# GPSReceiver_Kenwood710.net
KiCad netlist of a schematic drawn in EAGLE
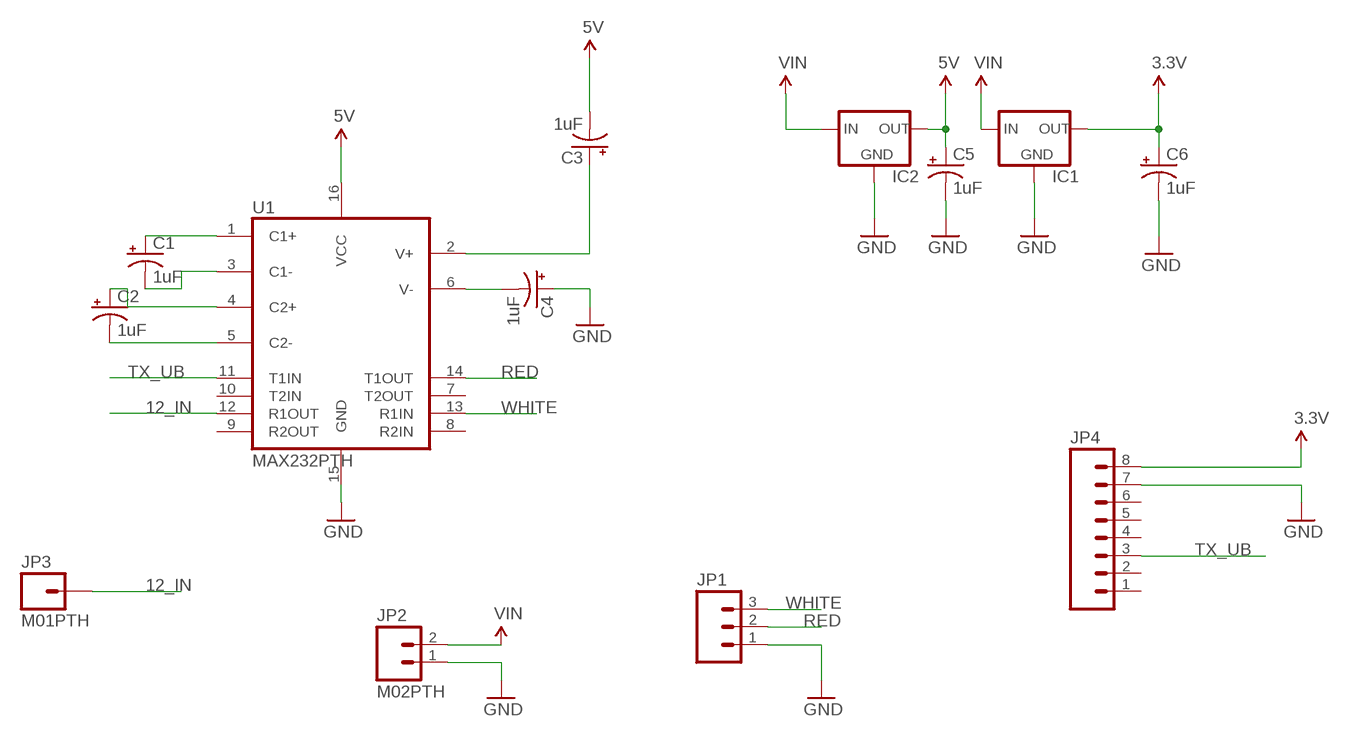
[diagram p0: schematic, sheet 1]

(export (version "E")
  (design (tool "Eeschema 10.0.6"))
  (components
    (comp (ref "C1")
      (value "1uF")
      (footprint "eagle-import:CPOL-RADIAL-10UF-25V")
      (libsource (lib "eagle-import") (part "CAP_POLPTH2"))
    )
    (comp (ref "C2")
      (value "1uF")
      (footprint "eagle-import:CPOL-RADIAL-10UF-25V")
      (libsource (lib "eagle-import") (part "CAP_POLPTH2"))
    )
    (comp (ref "C3")
      (value "1uF")
      (footprint "eagle-import:CPOL-RADIAL-10UF-25V")
      (libsource (lib "eagle-import") (part "CAP_POLPTH2"))
    )
    (comp (ref "C4")
      (value "1uF")
      (footprint "eagle-import:CPOL-RADIAL-10UF-25V")
      (libsource (lib "eagle-import") (part "CAP_POLPTH2"))
    )
    (comp (ref "C5")
      (value "1uF")
      (footprint "eagle-import:CPOL-RADIAL-10UF-25V")
      (libsource (lib "eagle-import") (part "CAP_POLPTH2"))
    )
    (comp (ref "C6")
      (value "1uF")
      (footprint "eagle-import:CPOL-RADIAL-10UF-25V")
      (libsource (lib "eagle-import") (part "CAP_POLPTH2"))
    )
    (comp (ref "IC1")
      (value "V_REG_78XX-TO-220")
      (footprint "eagle-import:TO-220-ALT")
      (libsource (lib "eagle-import") (part "V_REG_78XX-TO-220"))
    )
    (comp (ref "IC2")
      (value "V_REG_78XX-TO-220")
      (footprint "eagle-import:TO-220-ALT")
      (libsource (lib "eagle-import") (part "V_REG_78XX-TO-220"))
    )
    (comp (ref "JP1")
      (value "M03PTH")
      (footprint "eagle-import:1X03")
      (libsource (lib "eagle-import") (part "M03PTH"))
    )
    (comp (ref "JP2")
      (value "M02PTH")
      (footprint "eagle-import:1X02")
      (libsource (lib "eagle-import") (part "M02PTH"))
    )
    (comp (ref "JP3")
      (value "M01PTH")
      (footprint "eagle-import:1X01")
      (libsource (lib "eagle-import") (part "M01PTH"))
    )
    (comp (ref "JP4")
      (value "M08LOCK")
      (footprint "eagle-import:1X08_LOCK")
      (libsource (lib "eagle-import") (part "M08LOCK"))
    )
    (comp (ref "U1")
      (value "MAX232PTH")
      (footprint "eagle-import:DIL16")
      (libsource (lib "eagle-import") (part "MAX232PTH"))
    )
  )
  (nets
    (net (code "1") (name "/12_IN") (class "Default")
      (node (ref "JP3") (pin "1") (pinfunction "1_1") (pintype "passive"))
      (node (ref "U1") (pin "12") (pinfunction "R1OUT_12") (pintype "output"))
    )
    (net (code "2") (name "/RED") (class "Default")
      (node (ref "JP1") (pin "2") (pinfunction "2_2") (pintype "passive"))
      (node (ref "U1") (pin "14") (pinfunction "T1OUT_14") (pintype "output"))
    )
    (net (code "3") (name "/TX_UB") (class "Default")
      (node (ref "JP4") (pin "3") (pinfunction "3_3") (pintype "passive"))
      (node (ref "U1") (pin "11") (pinfunction "T1IN_11") (pintype "input"))
    )
    (net (code "4") (name "/WHITE") (class "Default")
      (node (ref "JP1") (pin "3") (pinfunction "3_3") (pintype "passive"))
      (node (ref "U1") (pin "13") (pinfunction "R1IN_13") (pintype "input"))
    )
    (net (code "5") (name "3.3V") (class "Default")
      (node (ref "C6") (pin "1") (pinfunction "+_1") (pintype "passive"))
      (node (ref "IC1") (pin "OUT") (pinfunction "OUT_OUT") (pintype "output"))
      (node (ref "JP4") (pin "8") (pinfunction "8_8") (pintype "passive"))
    )
    (net (code "6") (name "5V") (class "Default")
      (node (ref "C3") (pin "2") (pinfunction "-_2") (pintype "passive"))
      (node (ref "C5") (pin "1") (pinfunction "+_1") (pintype "passive"))
      (node (ref "IC2") (pin "OUT") (pinfunction "OUT_OUT") (pintype "output"))
      (node (ref "U1") (pin "16") (pinfunction "VCC_16") (pintype "bidirectional"))
    )
    (net (code "7") (name "GND") (class "Default")
      (node (ref "C4") (pin "1") (pinfunction "+_1") (pintype "passive"))
      (node (ref "C5") (pin "2") (pinfunction "-_2") (pintype "passive"))
      (node (ref "C6") (pin "2") (pinfunction "-_2") (pintype "passive"))
      (node (ref "IC1") (pin "GND") (pinfunction "GND_GND") (pintype "input"))
      (node (ref "IC2") (pin "GND") (pinfunction "GND_GND") (pintype "input"))
      (node (ref "JP1") (pin "1") (pinfunction "1_1") (pintype "passive"))
      (node (ref "JP2") (pin "1") (pinfunction "1_1") (pintype "passive"))
      (node (ref "JP4") (pin "7") (pinfunction "7_7") (pintype "passive"))
      (node (ref "U1") (pin "15") (pinfunction "GND_15") (pintype "bidirectional"))
    )
    (net (code "8") (name "Net-(C1-+)") (class "Default")
      (node (ref "C1") (pin "1") (pinfunction "+_1") (pintype "passive"))
      (node (ref "U1") (pin "1") (pinfunction "C1+_1") (pintype "bidirectional"))
    )
    (net (code "9") (name "Net-(C1--)") (class "Default")
      (node (ref "C1") (pin "2") (pinfunction "-_2") (pintype "passive"))
      (node (ref "U1") (pin "3") (pinfunction "C1-_3") (pintype "bidirectional"))
    )
    (net (code "10") (name "Net-(C2-+)") (class "Default")
      (node (ref "C2") (pin "1") (pinfunction "+_1") (pintype "passive"))
      (node (ref "U1") (pin "4") (pinfunction "C2+_4") (pintype "bidirectional"))
    )
    (net (code "11") (name "Net-(C2--)") (class "Default")
      (node (ref "C2") (pin "2") (pinfunction "-_2") (pintype "passive"))
      (node (ref "U1") (pin "5") (pinfunction "C2-_5") (pintype "bidirectional"))
    )
    (net (code "12") (name "Net-(C3-+)") (class "Default")
      (node (ref "C3") (pin "1") (pinfunction "+_1") (pintype "passive"))
      (node (ref "U1") (pin "2") (pinfunction "V+_2") (pintype "bidirectional"))
    )
    (net (code "13") (name "Net-(C4--)") (class "Default")
      (node (ref "C4") (pin "2") (pinfunction "-_2") (pintype "passive"))
      (node (ref "U1") (pin "6") (pinfunction "V-_6") (pintype "bidirectional"))
    )
    (net (code "14") (name "VIN") (class "Default")
      (node (ref "IC1") (pin "IN") (pinfunction "IN_IN") (pintype "input"))
      (node (ref "IC2") (pin "IN") (pinfunction "IN_IN") (pintype "input"))
      (node (ref "JP2") (pin "2") (pinfunction "2_2") (pintype "passive"))
    )
    (net (code "15") (name "unconnected-(JP4-Pad1)") (class "Default")
      (node (ref "JP4") (pin "1") (pinfunction "1_1") (pintype "passive"))
    )
    (net (code "16") (name "unconnected-(JP4-Pad2)") (class "Default")
      (node (ref "JP4") (pin "2") (pinfunction "2_2") (pintype "passive"))
    )
    (net (code "17") (name "unconnected-(JP4-Pad4)") (class "Default")
      (node (ref "JP4") (pin "4") (pinfunction "4_4") (pintype "passive"))
    )
    (net (code "18") (name "unconnected-(JP4-Pad5)") (class "Default")
      (node (ref "JP4") (pin "5") (pinfunction "5_5") (pintype "passive"))
    )
    (net (code "19") (name "unconnected-(JP4-Pad6)") (class "Default")
      (node (ref "JP4") (pin "6") (pinfunction "6_6") (pintype "passive"))
    )
    (net (code "20") (name "unconnected-(U1-R2IN-Pad8)") (class "Default")
      (node (ref "U1") (pin "8") (pinfunction "R2IN_8") (pintype "input"))
    )
    (net (code "21") (name "unconnected-(U1-R2OUT-Pad9)") (class "Default")
      (node (ref "U1") (pin "9") (pinfunction "R2OUT_9") (pintype "output"))
    )
    (net (code "22") (name "unconnected-(U1-T2IN-Pad10)") (class "Default")
      (node (ref "U1") (pin "10") (pinfunction "T2IN_10") (pintype "input"))
    )
    (net (code "23") (name "unconnected-(U1-T2OUT-Pad7)") (class "Default")
      (node (ref "U1") (pin "7") (pinfunction "T2OUT_7") (pintype "output"))
    )
  )
)
